# control.net
KiCad netlist of a schematic drawn in EAGLE
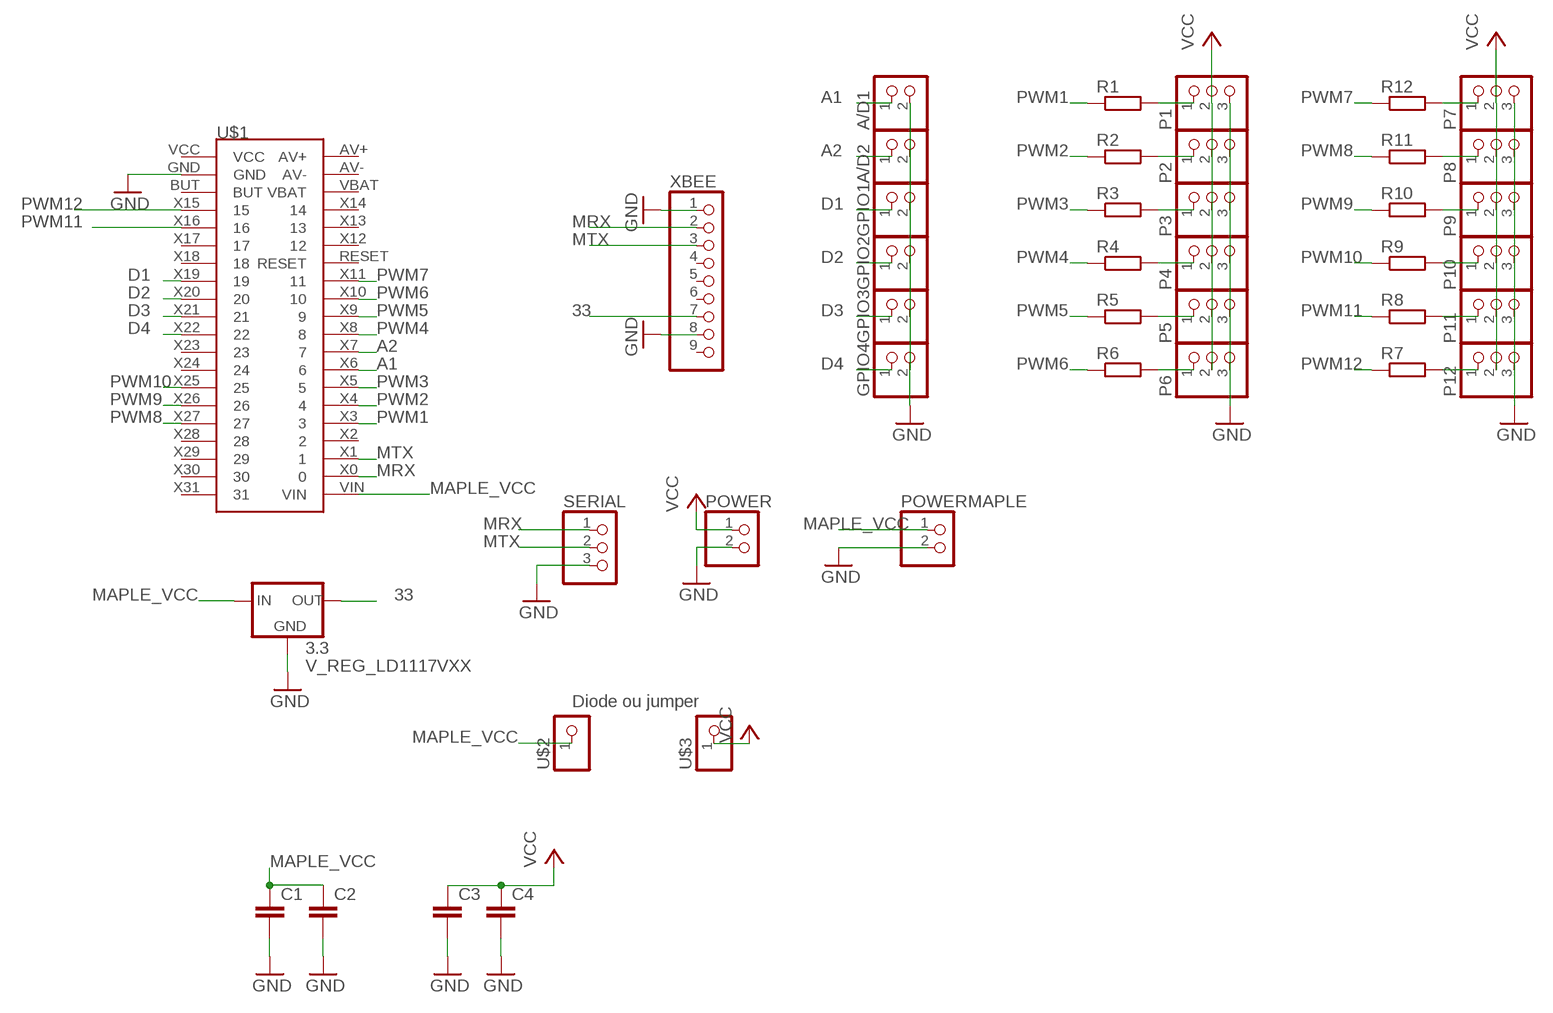
[diagram p0: schematic, sheet 1]

(export (version "E")
  (design (tool "Eeschema 10.0.6"))
  (components
    (comp (ref "3.3")
      (value "V_REG_LD1117VXX")
      (footprint "eagle-import:78XXL")
      (libsource (lib "eagle-import") (part "V_REG_LD1117VXX"))
    )
    (comp (ref "A/D1")
      (value "CONNEC_1X02")
      (footprint "eagle-import:CONNEC_1X02")
      (libsource (lib "eagle-import") (part "CONNEC_1X02"))
    )
    (comp (ref "A/D2")
      (value "CONNEC_1X02")
      (footprint "eagle-import:CONNEC_1X02")
      (libsource (lib "eagle-import") (part "CONNEC_1X02"))
    )
    (comp (ref "C1")
      (value "C-EU075-032X103")
      (footprint "eagle-import:C075-032X103")
      (libsource (lib "eagle-import") (part "C-EU075-032X103"))
    )
    (comp (ref "C2")
      (value "C-EU075-032X103")
      (footprint "eagle-import:C075-032X103")
      (libsource (lib "eagle-import") (part "C-EU075-032X103"))
    )
    (comp (ref "C3")
      (value "C-EU075-032X103")
      (footprint "eagle-import:C075-032X103")
      (libsource (lib "eagle-import") (part "C-EU075-032X103"))
    )
    (comp (ref "C4")
      (value "C-EU075-032X103")
      (footprint "eagle-import:C075-032X103")
      (libsource (lib "eagle-import") (part "C-EU075-032X103"))
    )
    (comp (ref "GPIO1")
      (value "CONNEC_1X02")
      (footprint "eagle-import:CONNEC_1X02")
      (libsource (lib "eagle-import") (part "CONNEC_1X02"))
    )
    (comp (ref "GPIO2")
      (value "CONNEC_1X02")
      (footprint "eagle-import:CONNEC_1X02")
      (libsource (lib "eagle-import") (part "CONNEC_1X02"))
    )
    (comp (ref "GPIO3")
      (value "CONNEC_1X02")
      (footprint "eagle-import:CONNEC_1X02")
      (libsource (lib "eagle-import") (part "CONNEC_1X02"))
    )
    (comp (ref "GPIO4")
      (value "CONNEC_1X02")
      (footprint "eagle-import:CONNEC_1X02")
      (libsource (lib "eagle-import") (part "CONNEC_1X02"))
    )
    (comp (ref "P1")
      (value "CONNEC_1X03")
      (footprint "eagle-import:CONNEC_1X03")
      (libsource (lib "eagle-import") (part "CONNEC_1X03"))
    )
    (comp (ref "P2")
      (value "CONNEC_1X03")
      (footprint "eagle-import:CONNEC_1X03")
      (libsource (lib "eagle-import") (part "CONNEC_1X03"))
    )
    (comp (ref "P3")
      (value "CONNEC_1X03")
      (footprint "eagle-import:CONNEC_1X03")
      (libsource (lib "eagle-import") (part "CONNEC_1X03"))
    )
    (comp (ref "P4")
      (value "CONNEC_1X03")
      (footprint "eagle-import:CONNEC_1X03")
      (libsource (lib "eagle-import") (part "CONNEC_1X03"))
    )
    (comp (ref "P5")
      (value "CONNEC_1X03")
      (footprint "eagle-import:CONNEC_1X03")
      (libsource (lib "eagle-import") (part "CONNEC_1X03"))
    )
    (comp (ref "P6")
      (value "CONNEC_1X03")
      (footprint "eagle-import:CONNEC_1X03")
      (libsource (lib "eagle-import") (part "CONNEC_1X03"))
    )
    (comp (ref "P7")
      (value "CONNEC_1X03")
      (footprint "eagle-import:CONNEC_1X03")
      (libsource (lib "eagle-import") (part "CONNEC_1X03"))
    )
    (comp (ref "P8")
      (value "CONNEC_1X03")
      (footprint "eagle-import:CONNEC_1X03")
      (libsource (lib "eagle-import") (part "CONNEC_1X03"))
    )
    (comp (ref "P9")
      (value "CONNEC_1X03")
      (footprint "eagle-import:CONNEC_1X03")
      (libsource (lib "eagle-import") (part "CONNEC_1X03"))
    )
    (comp (ref "P10")
      (value "CONNEC_1X03")
      (footprint "eagle-import:CONNEC_1X03")
      (libsource (lib "eagle-import") (part "CONNEC_1X03"))
    )
    (comp (ref "P11")
      (value "CONNEC_1X03")
      (footprint "eagle-import:CONNEC_1X03")
      (libsource (lib "eagle-import") (part "CONNEC_1X03"))
    )
    (comp (ref "P12")
      (value "CONNEC_1X03")
      (footprint "eagle-import:CONNEC_1X03")
      (libsource (lib "eagle-import") (part "CONNEC_1X03"))
    )
    (comp (ref "POWER")
      (value "CONNEC_1X02")
      (footprint "eagle-import:CONNEC_1X02")
      (libsource (lib "eagle-import") (part "CONNEC_1X02"))
    )
    (comp (ref "POWERMAPLE")
      (value "CONNEC_1X02")
      (footprint "eagle-import:CONNEC_1X02")
      (libsource (lib "eagle-import") (part "CONNEC_1X02"))
    )
    (comp (ref "R1")
      (value "RESISTANCE-R0805")
      (footprint "eagle-import:R0805")
      (libsource (lib "eagle-import") (part "RESISTANCE-R0805"))
    )
    (comp (ref "R2")
      (value "RESISTANCE-R0805")
      (footprint "eagle-import:R0805")
      (libsource (lib "eagle-import") (part "RESISTANCE-R0805"))
    )
    (comp (ref "R3")
      (value "RESISTANCE-R0805")
      (footprint "eagle-import:R0805")
      (libsource (lib "eagle-import") (part "RESISTANCE-R0805"))
    )
    (comp (ref "R4")
      (value "RESISTANCE-R0805")
      (footprint "eagle-import:R0805")
      (libsource (lib "eagle-import") (part "RESISTANCE-R0805"))
    )
    (comp (ref "R5")
      (value "RESISTANCE-R0805")
      (footprint "eagle-import:R0805")
      (libsource (lib "eagle-import") (part "RESISTANCE-R0805"))
    )
    (comp (ref "R6")
      (value "RESISTANCE-R0805")
      (footprint "eagle-import:R0805")
      (libsource (lib "eagle-import") (part "RESISTANCE-R0805"))
    )
    (comp (ref "R7")
      (value "RESISTANCE-R0805")
      (footprint "eagle-import:R0805")
      (libsource (lib "eagle-import") (part "RESISTANCE-R0805"))
    )
    (comp (ref "R8")
      (value "RESISTANCE-R0805")
      (footprint "eagle-import:R0805")
      (libsource (lib "eagle-import") (part "RESISTANCE-R0805"))
    )
    (comp (ref "R9")
      (value "RESISTANCE-R0805")
      (footprint "eagle-import:R0805")
      (libsource (lib "eagle-import") (part "RESISTANCE-R0805"))
    )
    (comp (ref "R10")
      (value "RESISTANCE-R0805")
      (footprint "eagle-import:R0805")
      (libsource (lib "eagle-import") (part "RESISTANCE-R0805"))
    )
    (comp (ref "R11")
      (value "RESISTANCE-R0805")
      (footprint "eagle-import:R0805")
      (libsource (lib "eagle-import") (part "RESISTANCE-R0805"))
    )
    (comp (ref "R12")
      (value "RESISTANCE-R0805")
      (footprint "eagle-import:R0805")
      (libsource (lib "eagle-import") (part "RESISTANCE-R0805"))
    )
    (comp (ref "SERIAL")
      (value "CONNEC_1X03")
      (footprint "eagle-import:CONNEC_1X03")
      (libsource (lib "eagle-import") (part "CONNEC_1X03"))
    )
    (comp (ref "U$1")
      (value "MAPLE_MINI")
      (footprint "eagle-import:CONNEC_2X20")
      (libsource (lib "eagle-import") (part "MAPLE_MINI"))
    )
    (comp (ref "U$2")
      (value "CONNEC_1X01")
      (footprint "eagle-import:CONNEC_1X01")
      (libsource (lib "eagle-import") (part "CONNEC_1X01"))
    )
    (comp (ref "U$3")
      (value "CONNEC_1X01")
      (footprint "eagle-import:CONNEC_1X01")
      (libsource (lib "eagle-import") (part "CONNEC_1X01"))
    )
    (comp (ref "XBEE")
      (value "CONNEC_1X09")
      (footprint "eagle-import:CONNEC_1X09")
      (libsource (lib "eagle-import") (part "CONNEC_1X09"))
    )
  )
  (nets
    (net (code "1") (name "/33") (class "Default")
      (node (ref "3.3") (pin "GND") (pinfunction "OUT_GND") (pintype "output"))
      (node (ref "XBEE") (pin "7") (pinfunction "7_7") (pintype "passive"))
    )
    (net (code "2") (name "/A1") (class "Default")
      (node (ref "A/D1") (pin "1") (pinfunction "1_1") (pintype "passive"))
      (node (ref "U$1") (pin "X6") (pinfunction "6_X6") (pintype "bidirectional"))
    )
    (net (code "3") (name "/A2") (class "Default")
      (node (ref "A/D2") (pin "1") (pinfunction "1_1") (pintype "passive"))
      (node (ref "U$1") (pin "X7") (pinfunction "7_X7") (pintype "bidirectional"))
    )
    (net (code "4") (name "/D1") (class "Default")
      (node (ref "GPIO1") (pin "1") (pinfunction "1_1") (pintype "passive"))
      (node (ref "U$1") (pin "X19") (pinfunction "19_X19") (pintype "bidirectional"))
    )
    (net (code "5") (name "/D2") (class "Default")
      (node (ref "GPIO2") (pin "1") (pinfunction "1_1") (pintype "passive"))
      (node (ref "U$1") (pin "X20") (pinfunction "20_X20") (pintype "bidirectional"))
    )
    (net (code "6") (name "/D3") (class "Default")
      (node (ref "GPIO3") (pin "1") (pinfunction "1_1") (pintype "passive"))
      (node (ref "U$1") (pin "X21") (pinfunction "21_X21") (pintype "bidirectional"))
    )
    (net (code "7") (name "/D4") (class "Default")
      (node (ref "GPIO4") (pin "1") (pinfunction "1_1") (pintype "passive"))
      (node (ref "U$1") (pin "X22") (pinfunction "22_X22") (pintype "bidirectional"))
    )
    (net (code "8") (name "/MAPLE_VCC") (class "Default")
      (node (ref "3.3") (pin "OUT") (pinfunction "IN_OUT") (pintype "input"))
      (node (ref "C1") (pin "1") (pinfunction "1_1") (pintype "passive"))
      (node (ref "C2") (pin "1") (pinfunction "1_1") (pintype "passive"))
      (node (ref "POWERMAPLE") (pin "1") (pinfunction "1_1") (pintype "passive"))
      (node (ref "U$1") (pin "VIN") (pinfunction "VIN_VIN") (pintype "bidirectional"))
      (node (ref "U$2") (pin "1") (pinfunction "1_1") (pintype "passive"))
    )
    (net (code "9") (name "/MRX") (class "Default")
      (node (ref "SERIAL") (pin "1") (pinfunction "1_1") (pintype "passive"))
      (node (ref "U$1") (pin "X0") (pinfunction "0_X0") (pintype "bidirectional"))
      (node (ref "XBEE") (pin "2") (pinfunction "2_2") (pintype "passive"))
    )
    (net (code "10") (name "/MTX") (class "Default")
      (node (ref "SERIAL") (pin "2") (pinfunction "2_2") (pintype "passive"))
      (node (ref "U$1") (pin "X1") (pinfunction "1_X1") (pintype "bidirectional"))
      (node (ref "XBEE") (pin "3") (pinfunction "3_3") (pintype "passive"))
    )
    (net (code "11") (name "/PWM1") (class "Default")
      (node (ref "R1") (pin "1") (pinfunction "1_1") (pintype "passive"))
      (node (ref "U$1") (pin "X3") (pinfunction "3_X3") (pintype "bidirectional"))
    )
    (net (code "12") (name "/PWM2") (class "Default")
      (node (ref "R2") (pin "1") (pinfunction "1_1") (pintype "passive"))
      (node (ref "U$1") (pin "X4") (pinfunction "4_X4") (pintype "bidirectional"))
    )
    (net (code "13") (name "/PWM3") (class "Default")
      (node (ref "R3") (pin "1") (pinfunction "1_1") (pintype "passive"))
      (node (ref "U$1") (pin "X5") (pinfunction "5_X5") (pintype "bidirectional"))
    )
    (net (code "14") (name "/PWM4") (class "Default")
      (node (ref "R4") (pin "1") (pinfunction "1_1") (pintype "passive"))
      (node (ref "U$1") (pin "X8") (pinfunction "8_X8") (pintype "bidirectional"))
    )
    (net (code "15") (name "/PWM5") (class "Default")
      (node (ref "R5") (pin "1") (pinfunction "1_1") (pintype "passive"))
      (node (ref "U$1") (pin "X9") (pinfunction "9_X9") (pintype "bidirectional"))
    )
    (net (code "16") (name "/PWM6") (class "Default")
      (node (ref "R6") (pin "1") (pinfunction "1_1") (pintype "passive"))
      (node (ref "U$1") (pin "X10") (pinfunction "10_X10") (pintype "bidirectional"))
    )
    (net (code "17") (name "/PWM7") (class "Default")
      (node (ref "R12") (pin "1") (pinfunction "1_1") (pintype "passive"))
      (node (ref "U$1") (pin "X11") (pinfunction "11_X11") (pintype "bidirectional"))
    )
    (net (code "18") (name "/PWM8") (class "Default")
      (node (ref "R11") (pin "1") (pinfunction "1_1") (pintype "passive"))
      (node (ref "U$1") (pin "X27") (pinfunction "27_X27") (pintype "bidirectional"))
    )
    (net (code "19") (name "/PWM9") (class "Default")
      (node (ref "R10") (pin "1") (pinfunction "1_1") (pintype "passive"))
      (node (ref "U$1") (pin "X26") (pinfunction "26_X26") (pintype "bidirectional"))
    )
    (net (code "20") (name "/PWM10") (class "Default")
      (node (ref "R9") (pin "1") (pinfunction "1_1") (pintype "passive"))
      (node (ref "U$1") (pin "X25") (pinfunction "25_X25") (pintype "bidirectional"))
    )
    (net (code "21") (name "/PWM11") (class "Default")
      (node (ref "R8") (pin "1") (pinfunction "1_1") (pintype "passive"))
      (node (ref "U$1") (pin "X16") (pinfunction "16_X16") (pintype "bidirectional"))
    )
    (net (code "22") (name "/PWM12") (class "Default")
      (node (ref "R7") (pin "1") (pinfunction "1_1") (pintype "passive"))
      (node (ref "U$1") (pin "X15") (pinfunction "15_X15") (pintype "bidirectional"))
    )
    (net (code "23") (name "GND") (class "Default")
      (node (ref "3.3") (pin "IN") (pinfunction "GND_IN") (pintype "input"))
      (node (ref "A/D1") (pin "2") (pinfunction "2_2") (pintype "passive"))
      (node (ref "A/D2") (pin "2") (pinfunction "2_2") (pintype "passive"))
      (node (ref "C1") (pin "2") (pinfunction "2_2") (pintype "passive"))
      (node (ref "C2") (pin "2") (pinfunction "2_2") (pintype "passive"))
      (node (ref "C3") (pin "2") (pinfunction "2_2") (pintype "passive"))
      (node (ref "C4") (pin "2") (pinfunction "2_2") (pintype "passive"))
      (node (ref "GPIO1") (pin "2") (pinfunction "2_2") (pintype "passive"))
      (node (ref "GPIO2") (pin "2") (pinfunction "2_2") (pintype "passive"))
      (node (ref "GPIO3") (pin "2") (pinfunction "2_2") (pintype "passive"))
      (node (ref "GPIO4") (pin "2") (pinfunction "2_2") (pintype "passive"))
      (node (ref "P1") (pin "3") (pinfunction "3_3") (pintype "passive"))
      (node (ref "P10") (pin "3") (pinfunction "3_3") (pintype "passive"))
      (node (ref "P11") (pin "3") (pinfunction "3_3") (pintype "passive"))
      (node (ref "P12") (pin "3") (pinfunction "3_3") (pintype "passive"))
      (node (ref "P2") (pin "3") (pinfunction "3_3") (pintype "passive"))
      (node (ref "P3") (pin "3") (pinfunction "3_3") (pintype "passive"))
      (node (ref "P4") (pin "3") (pinfunction "3_3") (pintype "passive"))
      (node (ref "P5") (pin "3") (pinfunction "3_3") (pintype "passive"))
      (node (ref "P6") (pin "3") (pinfunction "3_3") (pintype "passive"))
      (node (ref "P7") (pin "3") (pinfunction "3_3") (pintype "passive"))
      (node (ref "P8") (pin "3") (pinfunction "3_3") (pintype "passive"))
      (node (ref "P9") (pin "3") (pinfunction "3_3") (pintype "passive"))
      (node (ref "POWER") (pin "2") (pinfunction "2_2") (pintype "passive"))
      (node (ref "POWERMAPLE") (pin "2") (pinfunction "2_2") (pintype "passive"))
      (node (ref "SERIAL") (pin "3") (pinfunction "3_3") (pintype "passive"))
      (node (ref "U$1") (pin "GND") (pinfunction "GND_GND") (pintype "bidirectional"))
      (node (ref "XBEE") (pin "1") (pinfunction "1_1") (pintype "passive"))
      (node (ref "XBEE") (pin "8") (pinfunction "8_8") (pintype "passive"))
    )
    (net (code "24") (name "Net-(P1-Pad1)") (class "Default")
      (node (ref "P1") (pin "1") (pinfunction "1_1") (pintype "passive"))
      (node (ref "R1") (pin "2") (pinfunction "2_2") (pintype "passive"))
    )
    (net (code "25") (name "Net-(P2-Pad1)") (class "Default")
      (node (ref "P2") (pin "1") (pinfunction "1_1") (pintype "passive"))
      (node (ref "R2") (pin "2") (pinfunction "2_2") (pintype "passive"))
    )
    (net (code "26") (name "Net-(P3-Pad1)") (class "Default")
      (node (ref "P3") (pin "1") (pinfunction "1_1") (pintype "passive"))
      (node (ref "R3") (pin "2") (pinfunction "2_2") (pintype "passive"))
    )
    (net (code "27") (name "Net-(P4-Pad1)") (class "Default")
      (node (ref "P4") (pin "1") (pinfunction "1_1") (pintype "passive"))
      (node (ref "R4") (pin "2") (pinfunction "2_2") (pintype "passive"))
    )
    (net (code "28") (name "Net-(P5-Pad1)") (class "Default")
      (node (ref "P5") (pin "1") (pinfunction "1_1") (pintype "passive"))
      (node (ref "R5") (pin "2") (pinfunction "2_2") (pintype "passive"))
    )
    (net (code "29") (name "Net-(P6-Pad1)") (class "Default")
      (node (ref "P6") (pin "1") (pinfunction "1_1") (pintype "passive"))
      (node (ref "R6") (pin "2") (pinfunction "2_2") (pintype "passive"))
    )
    (net (code "30") (name "Net-(P7-Pad1)") (class "Default")
      (node (ref "P7") (pin "1") (pinfunction "1_1") (pintype "passive"))
      (node (ref "R12") (pin "2") (pinfunction "2_2") (pintype "passive"))
    )
    (net (code "31") (name "Net-(P8-Pad1)") (class "Default")
      (node (ref "P8") (pin "1") (pinfunction "1_1") (pintype "passive"))
      (node (ref "R11") (pin "2") (pinfunction "2_2") (pintype "passive"))
    )
    (net (code "32") (name "Net-(P9-Pad1)") (class "Default")
      (node (ref "P9") (pin "1") (pinfunction "1_1") (pintype "passive"))
      (node (ref "R10") (pin "2") (pinfunction "2_2") (pintype "passive"))
    )
    (net (code "33") (name "Net-(P10-Pad1)") (class "Default")
      (node (ref "P10") (pin "1") (pinfunction "1_1") (pintype "passive"))
      (node (ref "R9") (pin "2") (pinfunction "2_2") (pintype "passive"))
    )
    (net (code "34") (name "Net-(P11-Pad1)") (class "Default")
      (node (ref "P11") (pin "1") (pinfunction "1_1") (pintype "passive"))
      (node (ref "R8") (pin "2") (pinfunction "2_2") (pintype "passive"))
    )
    (net (code "35") (name "Net-(P12-Pad1)") (class "Default")
      (node (ref "P12") (pin "1") (pinfunction "1_1") (pintype "passive"))
      (node (ref "R7") (pin "2") (pinfunction "2_2") (pintype "passive"))
    )
    (net (code "36") (name "VCC") (class "Default")
      (node (ref "C3") (pin "1") (pinfunction "1_1") (pintype "passive"))
      (node (ref "C4") (pin "1") (pinfunction "1_1") (pintype "passive"))
      (node (ref "P1") (pin "2") (pinfunction "2_2") (pintype "passive"))
      (node (ref "P10") (pin "2") (pinfunction "2_2") (pintype "passive"))
      (node (ref "P11") (pin "2") (pinfunction "2_2") (pintype "passive"))
      (node (ref "P12") (pin "2") (pinfunction "2_2") (pintype "passive"))
      (node (ref "P2") (pin "2") (pinfunction "2_2") (pintype "passive"))
      (node (ref "P3") (pin "2") (pinfunction "2_2") (pintype "passive"))
      (node (ref "P4") (pin "2") (pinfunction "2_2") (pintype "passive"))
      (node (ref "P5") (pin "2") (pinfunction "2_2") (pintype "passive"))
      (node (ref "P6") (pin "2") (pinfunction "2_2") (pintype "passive"))
      (node (ref "P7") (pin "2") (pinfunction "2_2") (pintype "passive"))
      (node (ref "P8") (pin "2") (pinfunction "2_2") (pintype "passive"))
      (node (ref "P9") (pin "2") (pinfunction "2_2") (pintype "passive"))
      (node (ref "POWER") (pin "1") (pinfunction "1_1") (pintype "passive"))
      (node (ref "U$3") (pin "1") (pinfunction "1_1") (pintype "passive"))
    )
    (net (code "37") (name "unconnected-(U$1-2-PadX2)") (class "Default")
      (node (ref "U$1") (pin "X2") (pinfunction "2_X2") (pintype "bidirectional"))
    )
    (net (code "38") (name "unconnected-(U$1-12-PadX12)") (class "Default")
      (node (ref "U$1") (pin "X12") (pinfunction "12_X12") (pintype "bidirectional"))
    )
    (net (code "39") (name "unconnected-(U$1-13-PadX13)") (class "Default")
      (node (ref "U$1") (pin "X13") (pinfunction "13_X13") (pintype "bidirectional"))
    )
    (net (code "40") (name "unconnected-(U$1-14-PadX14)") (class "Default")
      (node (ref "U$1") (pin "X14") (pinfunction "14_X14") (pintype "bidirectional"))
    )
    (net (code "41") (name "unconnected-(U$1-17-PadX17)") (class "Default")
      (node (ref "U$1") (pin "X17") (pinfunction "17_X17") (pintype "bidirectional"))
    )
    (net (code "42") (name "unconnected-(U$1-18-PadX18)") (class "Default")
      (node (ref "U$1") (pin "X18") (pinfunction "18_X18") (pintype "bidirectional"))
    )
    (net (code "43") (name "unconnected-(U$1-23-PadX23)") (class "Default")
      (node (ref "U$1") (pin "X23") (pinfunction "23_X23") (pintype "bidirectional"))
    )
    (net (code "44") (name "unconnected-(U$1-24-PadX24)") (class "Default")
      (node (ref "U$1") (pin "X24") (pinfunction "24_X24") (pintype "bidirectional"))
    )
    (net (code "45") (name "unconnected-(U$1-28-PadX28)") (class "Default")
      (node (ref "U$1") (pin "X28") (pinfunction "28_X28") (pintype "bidirectional"))
    )
    (net (code "46") (name "unconnected-(U$1-29-PadX29)") (class "Default")
      (node (ref "U$1") (pin "X29") (pinfunction "29_X29") (pintype "bidirectional"))
    )
    (net (code "47") (name "unconnected-(U$1-30-PadX30)") (class "Default")
      (node (ref "U$1") (pin "X30") (pinfunction "30_X30") (pintype "bidirectional"))
    )
    (net (code "48") (name "unconnected-(U$1-31-PadX31)") (class "Default")
      (node (ref "U$1") (pin "X31") (pinfunction "31_X31") (pintype "bidirectional"))
    )
    (net (code "49") (name "unconnected-(U$1-PadAV+)") (class "Default")
      (node (ref "U$1") (pin "AV+") (pinfunction "AV+_AV+") (pintype "bidirectional"))
    )
    (net (code "50") (name "unconnected-(U$1-PadAV-)") (class "Default")
      (node (ref "U$1") (pin "AV-") (pinfunction "AV-_AV-") (pintype "bidirectional"))
    )
    (net (code "51") (name "unconnected-(U$1-PadBUT)") (class "Default")
      (node (ref "U$1") (pin "BUT") (pinfunction "BUT_BUT") (pintype "bidirectional"))
    )
    (net (code "52") (name "unconnected-(U$1-PadRESET)") (class "Default")
      (node (ref "U$1") (pin "RESET") (pinfunction "RESET_RESET") (pintype "bidirectional"))
    )
    (net (code "53") (name "unconnected-(U$1-PadVBAT)") (class "Default")
      (node (ref "U$1") (pin "VBAT") (pinfunction "VBAT_VBAT") (pintype "bidirectional"))
    )
    (net (code "54") (name "unconnected-(U$1-PadVCC)") (class "Default")
      (node (ref "U$1") (pin "VCC") (pinfunction "VCC_VCC") (pintype "bidirectional"))
    )
    (net (code "55") (name "unconnected-(XBEE-Pad4)") (class "Default")
      (node (ref "XBEE") (pin "4") (pinfunction "4_4") (pintype "passive"))
    )
    (net (code "56") (name "unconnected-(XBEE-Pad5)") (class "Default")
      (node (ref "XBEE") (pin "5") (pinfunction "5_5") (pintype "passive"))
    )
    (net (code "57") (name "unconnected-(XBEE-Pad6)") (class "Default")
      (node (ref "XBEE") (pin "6") (pinfunction "6_6") (pintype "passive"))
    )
    (net (code "58") (name "unconnected-(XBEE-Pad9)") (class "Default")
      (node (ref "XBEE") (pin "9") (pinfunction "9_9") (pintype "passive"))
    )
  )
)
